# Differential_driver.net
KiCad netlist of a schematic drawn in EAGLE
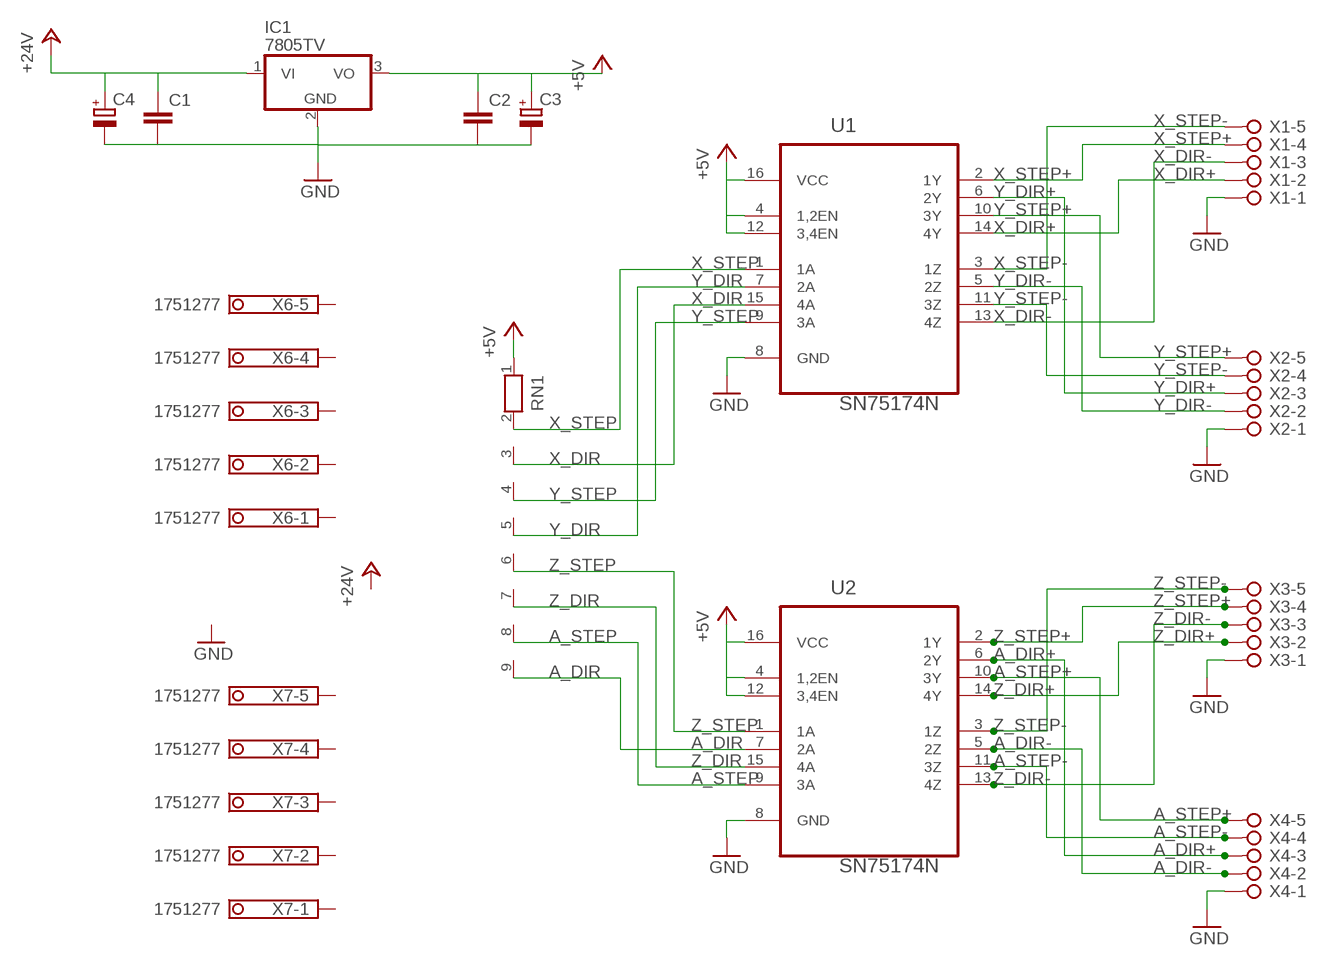
[diagram p0: schematic, sheet 1]

(export (version "E")
  (design (tool "Eeschema 10.0.6"))
  (components
    (comp (ref "C1")
      (value "C-EU025-025X050")
      (footprint "eagle-import:C025-025X050")
      (libsource (lib "eagle-import") (part "C-EU025-025X050"))
    )
    (comp (ref "C2")
      (value "C-EU025-025X050")
      (footprint "eagle-import:C025-025X050")
      (libsource (lib "eagle-import") (part "C-EU025-025X050"))
    )
    (comp (ref "C3")
      (value "CPOL-EUE2.5-5")
      (footprint "eagle-import:E2,5-5")
      (libsource (lib "eagle-import") (part "CPOL-EUE2.5-5"))
    )
    (comp (ref "C4")
      (value "CPOL-EUE2.5-5")
      (footprint "eagle-import:E2,5-5")
      (libsource (lib "eagle-import") (part "CPOL-EUE2.5-5"))
    )
    (comp (ref "IC1")
      (value "7805TV")
      (footprint "eagle-import:TO220V")
      (libsource (lib "eagle-import") (part "78TV05"))
    )
    (comp (ref "RN1")
      (value "RN08")
      (footprint "eagle-import:RN-9")
      (libsource (lib "eagle-import") (part "RN08"))
    )
    (comp (ref "U1")
      (value "SN75174N")
      (footprint "eagle-import:DIP254P762X508-16")
      (libsource (lib "eagle-import") (part "SN75174N"))
    )
    (comp (ref "U2")
      (value "SN75174N")
      (footprint "eagle-import:DIP254P762X508-16")
      (libsource (lib "eagle-import") (part "SN75174N"))
    )
    (comp (ref "X1")
      (value "W237-05P")
      (footprint "eagle-import:W237-5P")
      (libsource (lib "eagle-import") (part "W237-05P"))
    )
    (comp (ref "X2")
      (value "W237-05P")
      (footprint "eagle-import:W237-5P")
      (libsource (lib "eagle-import") (part "W237-05P"))
    )
    (comp (ref "X3")
      (value "W237-05P")
      (footprint "eagle-import:W237-5P")
      (libsource (lib "eagle-import") (part "W237-05P"))
    )
    (comp (ref "X4")
      (value "W237-05P")
      (footprint "eagle-import:W237-5P")
      (libsource (lib "eagle-import") (part "W237-05P"))
    )
    (comp (ref "X6")
      (value "1751277")
      (footprint "eagle-import:1751277")
      (libsource (lib "eagle-import") (part "1751277"))
    )
    (comp (ref "X7")
      (value "1751277")
      (footprint "eagle-import:1751277")
      (libsource (lib "eagle-import") (part "1751277"))
    )
  )
  (nets
    (net (code "1") (name "+5V") (class "Default")
      (node (ref "C2") (pin "1") (pinfunction "1_1") (pintype "passive"))
      (node (ref "C3") (pin "+") (pinfunction "+_+") (pintype "passive"))
      (node (ref "IC1") (pin "3") (pinfunction "VO_3") (pintype "passive"))
      (node (ref "RN1") (pin "1") (pinfunction "1_1") (pintype "passive"))
      (node (ref "U1") (pin "12") (pinfunction "3,4EN_12") (pintype "input"))
      (node (ref "U1") (pin "16") (pinfunction "VCC_16") (pintype "power_in"))
      (node (ref "U1") (pin "4") (pinfunction "1,2EN_4") (pintype "input"))
      (node (ref "U2") (pin "12") (pinfunction "3,4EN_12") (pintype "input"))
      (node (ref "U2") (pin "16") (pinfunction "VCC_16") (pintype "power_in"))
      (node (ref "U2") (pin "4") (pinfunction "1,2EN_4") (pintype "input"))
    )
    (net (code "2") (name "+24V") (class "Default")
      (node (ref "C1") (pin "1") (pinfunction "1_1") (pintype "passive"))
      (node (ref "C4") (pin "+") (pinfunction "+_+") (pintype "passive"))
      (node (ref "IC1") (pin "1") (pinfunction "VI_1") (pintype "input"))
    )
    (net (code "3") (name "/A_DIR") (class "Default")
      (node (ref "RN1") (pin "9") (pinfunction "9_9") (pintype "passive"))
      (node (ref "U2") (pin "7") (pinfunction "2A_7") (pintype "input"))
    )
    (net (code "4") (name "/A_DIR+") (class "Default")
      (node (ref "U2") (pin "6") (pinfunction "2Y_6") (pintype "output"))
      (node (ref "X4") (pin "3") (pinfunction "KL_3") (pintype "passive"))
    )
    (net (code "5") (name "/A_DIR-") (class "Default")
      (node (ref "U2") (pin "5") (pinfunction "2Z_5") (pintype "output"))
      (node (ref "X4") (pin "2") (pinfunction "KL_2") (pintype "passive"))
    )
    (net (code "6") (name "/A_STEP") (class "Default")
      (node (ref "RN1") (pin "8") (pinfunction "8_8") (pintype "passive"))
      (node (ref "U2") (pin "9") (pinfunction "3A_9") (pintype "input"))
    )
    (net (code "7") (name "/A_STEP+") (class "Default")
      (node (ref "U2") (pin "10") (pinfunction "3Y_10") (pintype "output"))
      (node (ref "X4") (pin "5") (pinfunction "KL_5") (pintype "passive"))
    )
    (net (code "8") (name "/A_STEP-") (class "Default")
      (node (ref "U2") (pin "11") (pinfunction "3Z_11") (pintype "output"))
      (node (ref "X4") (pin "4") (pinfunction "KL_4") (pintype "passive"))
    )
    (net (code "9") (name "/X_DIR") (class "Default")
      (node (ref "RN1") (pin "3") (pinfunction "3_3") (pintype "passive"))
      (node (ref "U1") (pin "15") (pinfunction "4A_15") (pintype "input"))
    )
    (net (code "10") (name "/X_DIR+") (class "Default")
      (node (ref "U1") (pin "14") (pinfunction "4Y_14") (pintype "output"))
      (node (ref "X1") (pin "2") (pinfunction "KL_2") (pintype "passive"))
    )
    (net (code "11") (name "/X_DIR-") (class "Default")
      (node (ref "U1") (pin "13") (pinfunction "4Z_13") (pintype "output"))
      (node (ref "X1") (pin "3") (pinfunction "KL_3") (pintype "passive"))
    )
    (net (code "12") (name "/X_STEP") (class "Default")
      (node (ref "RN1") (pin "2") (pinfunction "2_2") (pintype "passive"))
      (node (ref "U1") (pin "1") (pinfunction "1A_1") (pintype "input"))
    )
    (net (code "13") (name "/X_STEP+") (class "Default")
      (node (ref "U1") (pin "2") (pinfunction "1Y_2") (pintype "output"))
      (node (ref "X1") (pin "4") (pinfunction "KL_4") (pintype "passive"))
    )
    (net (code "14") (name "/X_STEP-") (class "Default")
      (node (ref "U1") (pin "3") (pinfunction "1Z_3") (pintype "output"))
      (node (ref "X1") (pin "5") (pinfunction "KL_5") (pintype "passive"))
    )
    (net (code "15") (name "/Y_DIR") (class "Default")
      (node (ref "RN1") (pin "5") (pinfunction "5_5") (pintype "passive"))
      (node (ref "U1") (pin "7") (pinfunction "2A_7") (pintype "input"))
    )
    (net (code "16") (name "/Y_DIR+") (class "Default")
      (node (ref "U1") (pin "6") (pinfunction "2Y_6") (pintype "output"))
      (node (ref "X2") (pin "3") (pinfunction "KL_3") (pintype "passive"))
    )
    (net (code "17") (name "/Y_DIR-") (class "Default")
      (node (ref "U1") (pin "5") (pinfunction "2Z_5") (pintype "output"))
      (node (ref "X2") (pin "2") (pinfunction "KL_2") (pintype "passive"))
    )
    (net (code "18") (name "/Y_STEP") (class "Default")
      (node (ref "RN1") (pin "4") (pinfunction "4_4") (pintype "passive"))
      (node (ref "U1") (pin "9") (pinfunction "3A_9") (pintype "input"))
    )
    (net (code "19") (name "/Y_STEP+") (class "Default")
      (node (ref "U1") (pin "10") (pinfunction "3Y_10") (pintype "output"))
      (node (ref "X2") (pin "5") (pinfunction "KL_5") (pintype "passive"))
    )
    (net (code "20") (name "/Y_STEP-") (class "Default")
      (node (ref "U1") (pin "11") (pinfunction "3Z_11") (pintype "output"))
      (node (ref "X2") (pin "4") (pinfunction "KL_4") (pintype "passive"))
    )
    (net (code "21") (name "/Z_DIR") (class "Default")
      (node (ref "RN1") (pin "7") (pinfunction "7_7") (pintype "passive"))
      (node (ref "U2") (pin "15") (pinfunction "4A_15") (pintype "input"))
    )
    (net (code "22") (name "/Z_DIR+") (class "Default")
      (node (ref "U2") (pin "14") (pinfunction "4Y_14") (pintype "output"))
      (node (ref "X3") (pin "2") (pinfunction "KL_2") (pintype "passive"))
    )
    (net (code "23") (name "/Z_DIR-") (class "Default")
      (node (ref "U2") (pin "13") (pinfunction "4Z_13") (pintype "output"))
      (node (ref "X3") (pin "3") (pinfunction "KL_3") (pintype "passive"))
    )
    (net (code "24") (name "/Z_STEP") (class "Default")
      (node (ref "RN1") (pin "6") (pinfunction "6_6") (pintype "passive"))
      (node (ref "U2") (pin "1") (pinfunction "1A_1") (pintype "input"))
    )
    (net (code "25") (name "/Z_STEP+") (class "Default")
      (node (ref "U2") (pin "2") (pinfunction "1Y_2") (pintype "output"))
      (node (ref "X3") (pin "4") (pinfunction "KL_4") (pintype "passive"))
    )
    (net (code "26") (name "/Z_STEP-") (class "Default")
      (node (ref "U2") (pin "3") (pinfunction "1Z_3") (pintype "output"))
      (node (ref "X3") (pin "5") (pinfunction "KL_5") (pintype "passive"))
    )
    (net (code "27") (name "GND") (class "Default")
      (node (ref "C1") (pin "2") (pinfunction "2_2") (pintype "passive"))
      (node (ref "C2") (pin "2") (pinfunction "2_2") (pintype "passive"))
      (node (ref "C3") (pin "-") (pinfunction "-_-") (pintype "passive"))
      (node (ref "C4") (pin "-") (pinfunction "-_-") (pintype "passive"))
      (node (ref "IC1") (pin "2") (pinfunction "GND_2") (pintype "passive"))
      (node (ref "U1") (pin "8") (pinfunction "GND_8") (pintype "passive"))
      (node (ref "U2") (pin "8") (pinfunction "GND_8") (pintype "passive"))
      (node (ref "X1") (pin "1") (pinfunction "KL_1") (pintype "passive"))
      (node (ref "X2") (pin "1") (pinfunction "KL_1") (pintype "passive"))
      (node (ref "X3") (pin "1") (pinfunction "KL_1") (pintype "passive"))
      (node (ref "X4") (pin "1") (pinfunction "KL_1") (pintype "passive"))
    )
    (net (code "28") (name "unconnected-(X6A-K-Pad1)") (class "Default")
      (node (ref "X6") (pin "1") (pinfunction "K_1") (pintype "passive"))
    )
    (net (code "29") (name "unconnected-(X6B-K-Pad2)") (class "Default")
      (node (ref "X6") (pin "2") (pinfunction "K_2") (pintype "passive"))
    )
    (net (code "30") (name "unconnected-(X6C-K-Pad3)") (class "Default")
      (node (ref "X6") (pin "3") (pinfunction "K_3") (pintype "passive"))
    )
    (net (code "31") (name "unconnected-(X6D-K-Pad4)") (class "Default")
      (node (ref "X6") (pin "4") (pinfunction "K_4") (pintype "passive"))
    )
    (net (code "32") (name "unconnected-(X6E-K-Pad5)") (class "Default")
      (node (ref "X6") (pin "5") (pinfunction "K_5") (pintype "passive"))
    )
    (net (code "33") (name "unconnected-(X7A-K-Pad1)") (class "Default")
      (node (ref "X7") (pin "1") (pinfunction "K_1") (pintype "passive"))
    )
    (net (code "34") (name "unconnected-(X7B-K-Pad2)") (class "Default")
      (node (ref "X7") (pin "2") (pinfunction "K_2") (pintype "passive"))
    )
    (net (code "35") (name "unconnected-(X7C-K-Pad3)") (class "Default")
      (node (ref "X7") (pin "3") (pinfunction "K_3") (pintype "passive"))
    )
    (net (code "36") (name "unconnected-(X7D-K-Pad4)") (class "Default")
      (node (ref "X7") (pin "4") (pinfunction "K_4") (pintype "passive"))
    )
    (net (code "37") (name "unconnected-(X7E-K-Pad5)") (class "Default")
      (node (ref "X7") (pin "5") (pinfunction "K_5") (pintype "passive"))
    )
  )
)
